# Honig_Sensor_Board_2_01.net
KiCad netlist of a schematic drawn in EAGLE
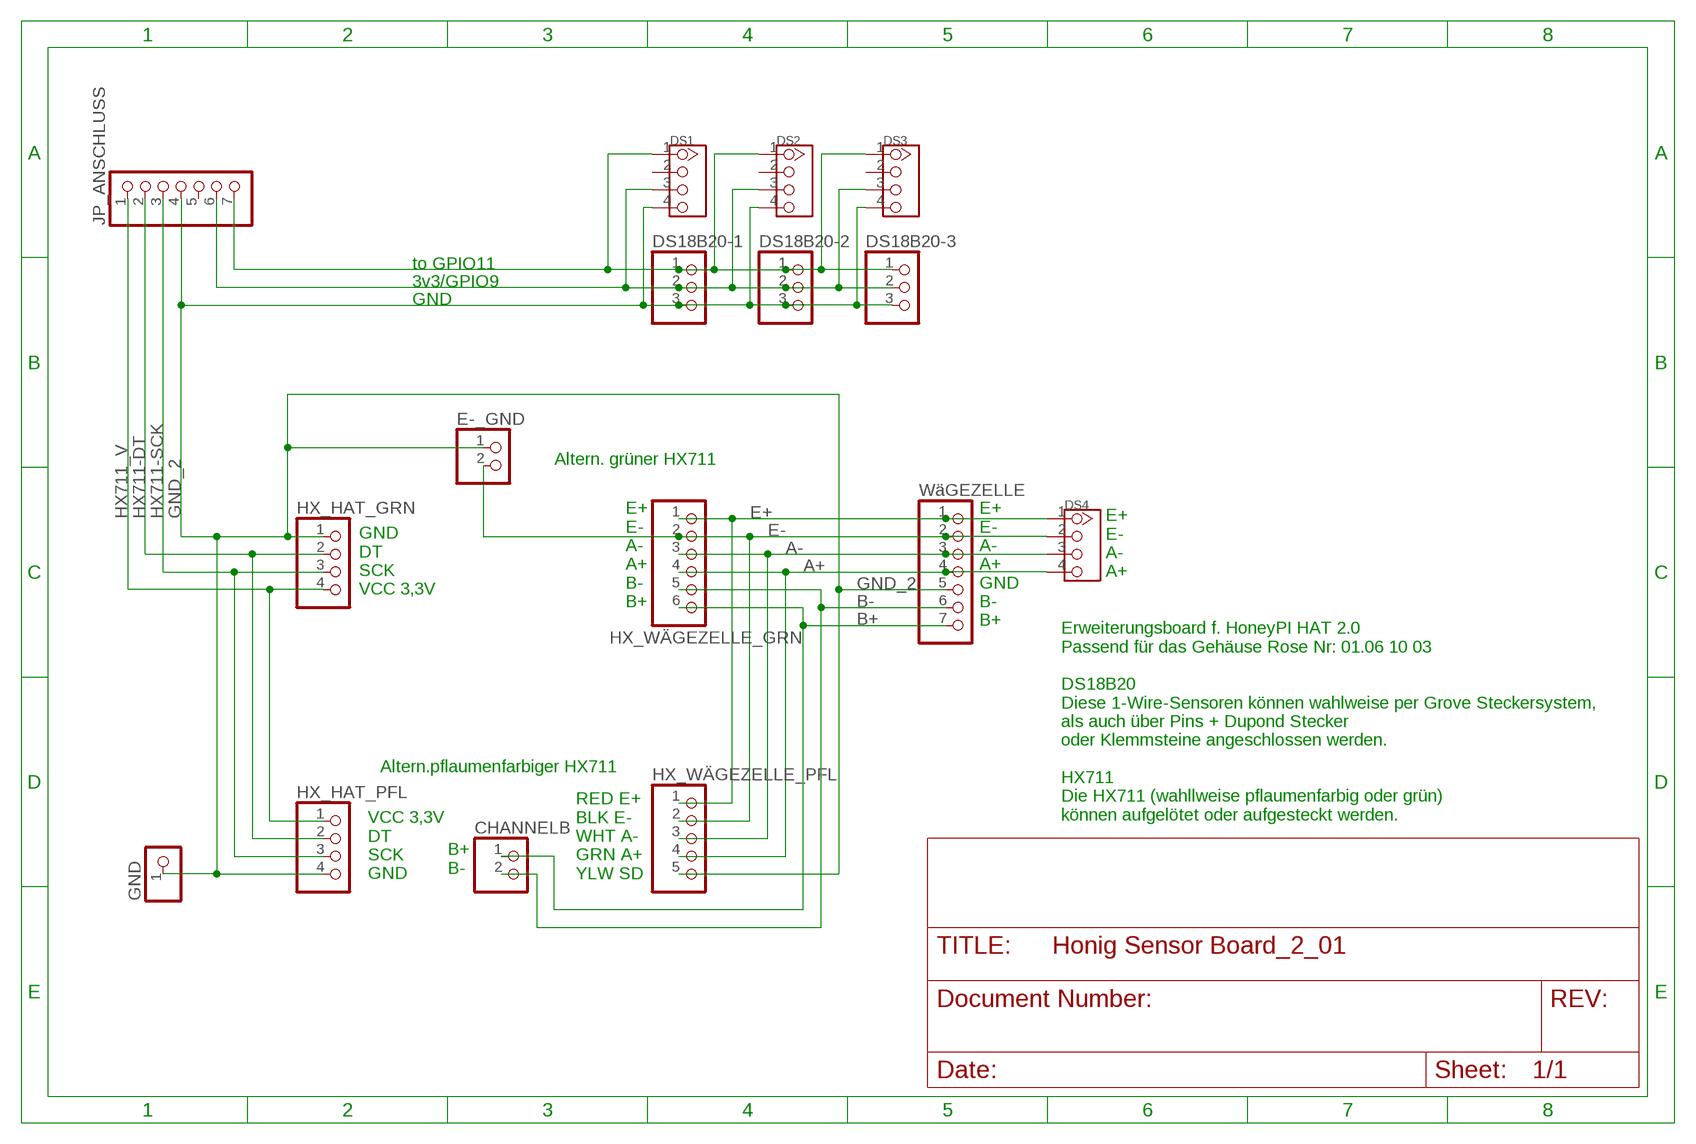
[diagram p0: schematic, sheet 1]

(export (version "E")
  (design (tool "Eeschema 10.0.6"))
  (components
    (comp (ref "CHANNELB")
      (value "PINHD-1X2")
      (footprint "eagle-import:1X02")
      (libsource (lib "eagle-import") (part "PINHD-1X2"))
    )
    (comp (ref "DS1")
      (value "TWIG-4P-2.0-2.0")
      (footprint "eagle-import:4P-2.0")
      (libsource (lib "eagle-import") (part "TWIG-4P-2.0-2.0"))
    )
    (comp (ref "DS2")
      (value "TWIG-4P-2.0-2.0")
      (footprint "eagle-import:4P-2.0")
      (libsource (lib "eagle-import") (part "TWIG-4P-2.0-2.0"))
    )
    (comp (ref "DS3")
      (value "TWIG-4P-2.0-2.0")
      (footprint "eagle-import:4P-2.0")
      (libsource (lib "eagle-import") (part "TWIG-4P-2.0-2.0"))
    )
    (comp (ref "DS4")
      (value "TWIG-4P-2.0-2.0")
      (footprint "eagle-import:4P-2.0")
      (libsource (lib "eagle-import") (part "TWIG-4P-2.0-2.0"))
    )
    (comp (ref "DS18B20-1")
      (value "PINHD-1X3")
      (footprint "eagle-import:1X03")
      (libsource (lib "eagle-import") (part "PINHD-1X3"))
    )
    (comp (ref "DS18B20-2")
      (value "PINHD-1X3")
      (footprint "eagle-import:1X03")
      (libsource (lib "eagle-import") (part "PINHD-1X3"))
    )
    (comp (ref "DS18B20-3")
      (value "PINHD-1X3")
      (footprint "eagle-import:1X03")
      (libsource (lib "eagle-import") (part "PINHD-1X3"))
    )
    (comp (ref "E-_GND")
      (value "PINHD-1X2")
      (footprint "eagle-import:1X02")
      (libsource (lib "eagle-import") (part "PINHD-1X2"))
    )
    (comp (ref "GND")
      (value "PINHD-1X1")
      (footprint "eagle-import:1X01")
      (libsource (lib "eagle-import") (part "PINHD-1X1"))
    )
    (comp (ref "HX_HAT_GRN")
      (value "PINHD-1X4")
      (footprint "eagle-import:1X04")
      (libsource (lib "eagle-import") (part "PINHD-1X4"))
    )
    (comp (ref "HX_HAT_PFL")
      (value "PINHD-1X4")
      (footprint "eagle-import:1X04")
      (libsource (lib "eagle-import") (part "PINHD-1X4"))
    )
    (comp (ref "HX_WÄGEZELLE_GRN")
      (value "PINHD-1X6")
      (footprint "eagle-import:1X06")
      (libsource (lib "eagle-import") (part "PINHD-1X6"))
    )
    (comp (ref "HX_WÄGEZELLE_PFL")
      (value "PINHD-1X5")
      (footprint "eagle-import:1X05")
      (libsource (lib "eagle-import") (part "PINHD-1X5"))
    )
    (comp (ref "JP_ANSCHLUSS")
      (value "PINHD-1X7")
      (footprint "eagle-import:1X07")
      (libsource (lib "eagle-import") (part "PINHD-1X7"))
    )
    (comp (ref "WäGEZELLE")
      (value "PINHD-1X7")
      (footprint "eagle-import:1X07")
      (libsource (lib "eagle-import") (part "PINHD-1X7"))
    )
  )
  (nets
    (net (code "1") (name "/A+") (class "Default")
      (node (ref "DS4") (pin "4") (pinfunction "4_4") (pintype "bidirectional"))
      (node (ref "HX_WÄGEZELLE_GRN") (pin "4") (pinfunction "4_4") (pintype "passive"))
      (node (ref "HX_WÄGEZELLE_PFL") (pin "4") (pinfunction "4_4") (pintype "passive"))
      (node (ref "WäGEZELLE") (pin "4") (pinfunction "4_4") (pintype "passive"))
    )
    (net (code "2") (name "/A-") (class "Default")
      (node (ref "DS4") (pin "3") (pinfunction "3_3") (pintype "bidirectional"))
      (node (ref "HX_WÄGEZELLE_GRN") (pin "3") (pinfunction "3_3") (pintype "passive"))
      (node (ref "HX_WÄGEZELLE_PFL") (pin "3") (pinfunction "3_3") (pintype "passive"))
      (node (ref "WäGEZELLE") (pin "3") (pinfunction "3_3") (pintype "passive"))
    )
    (net (code "3") (name "/B+") (class "Default")
      (node (ref "CHANNELB") (pin "1") (pinfunction "1_1") (pintype "passive"))
      (node (ref "HX_WÄGEZELLE_GRN") (pin "6") (pinfunction "6_6") (pintype "passive"))
      (node (ref "WäGEZELLE") (pin "7") (pinfunction "7_7") (pintype "passive"))
    )
    (net (code "4") (name "/B-") (class "Default")
      (node (ref "CHANNELB") (pin "2") (pinfunction "2_2") (pintype "passive"))
      (node (ref "HX_WÄGEZELLE_GRN") (pin "5") (pinfunction "5_5") (pintype "passive"))
      (node (ref "WäGEZELLE") (pin "6") (pinfunction "6_6") (pintype "passive"))
    )
    (net (code "5") (name "/E+") (class "Default")
      (node (ref "DS4") (pin "1") (pinfunction "1_1") (pintype "bidirectional"))
      (node (ref "HX_WÄGEZELLE_GRN") (pin "1") (pinfunction "1_1") (pintype "passive"))
      (node (ref "HX_WÄGEZELLE_PFL") (pin "1") (pinfunction "1_1") (pintype "passive"))
      (node (ref "WäGEZELLE") (pin "1") (pinfunction "1_1") (pintype "passive"))
    )
    (net (code "6") (name "/E-") (class "Default")
      (node (ref "DS4") (pin "2") (pinfunction "2_2") (pintype "bidirectional"))
      (node (ref "E-_GND") (pin "2") (pinfunction "2_2") (pintype "passive"))
      (node (ref "HX_WÄGEZELLE_GRN") (pin "2") (pinfunction "2_2") (pintype "passive"))
      (node (ref "HX_WÄGEZELLE_PFL") (pin "2") (pinfunction "2_2") (pintype "passive"))
      (node (ref "WäGEZELLE") (pin "2") (pinfunction "2_2") (pintype "passive"))
    )
    (net (code "7") (name "/GND_2") (class "Default")
      (node (ref "DS1") (pin "4") (pinfunction "4_4") (pintype "bidirectional"))
      (node (ref "DS18B20-1") (pin "3") (pinfunction "3_3") (pintype "passive"))
      (node (ref "DS18B20-2") (pin "3") (pinfunction "3_3") (pintype "passive"))
      (node (ref "DS18B20-3") (pin "3") (pinfunction "3_3") (pintype "passive"))
      (node (ref "DS2") (pin "4") (pinfunction "4_4") (pintype "bidirectional"))
      (node (ref "DS3") (pin "4") (pinfunction "4_4") (pintype "bidirectional"))
      (node (ref "E-_GND") (pin "1") (pinfunction "1_1") (pintype "passive"))
      (node (ref "GND") (pin "1") (pinfunction "1_1") (pintype "passive"))
      (node (ref "HX_HAT_GRN") (pin "1") (pinfunction "1_1") (pintype "passive"))
      (node (ref "HX_HAT_PFL") (pin "4") (pinfunction "4_4") (pintype "passive"))
      (node (ref "HX_WÄGEZELLE_PFL") (pin "5") (pinfunction "5_5") (pintype "passive"))
      (node (ref "JP_ANSCHLUSS") (pin "4") (pinfunction "4_4") (pintype "passive"))
      (node (ref "WäGEZELLE") (pin "5") (pinfunction "5_5") (pintype "passive"))
    )
    (net (code "8") (name "/HX711-DT") (class "Default")
      (node (ref "HX_HAT_GRN") (pin "2") (pinfunction "2_2") (pintype "passive"))
      (node (ref "HX_HAT_PFL") (pin "2") (pinfunction "2_2") (pintype "passive"))
      (node (ref "JP_ANSCHLUSS") (pin "2") (pinfunction "2_2") (pintype "passive"))
    )
    (net (code "9") (name "/HX711-SCK") (class "Default")
      (node (ref "HX_HAT_GRN") (pin "3") (pinfunction "3_3") (pintype "passive"))
      (node (ref "HX_HAT_PFL") (pin "3") (pinfunction "3_3") (pintype "passive"))
      (node (ref "JP_ANSCHLUSS") (pin "3") (pinfunction "3_3") (pintype "passive"))
    )
    (net (code "10") (name "/HX711_V") (class "Default")
      (node (ref "HX_HAT_GRN") (pin "4") (pinfunction "4_4") (pintype "passive"))
      (node (ref "HX_HAT_PFL") (pin "1") (pinfunction "1_1") (pintype "passive"))
      (node (ref "JP_ANSCHLUSS") (pin "1") (pinfunction "1_1") (pintype "passive"))
    )
    (net (code "11") (name "Net-(DS1-Pad1)") (class "Default")
      (node (ref "DS1") (pin "1") (pinfunction "1_1") (pintype "bidirectional"))
      (node (ref "DS18B20-1") (pin "1") (pinfunction "1_1") (pintype "passive"))
      (node (ref "DS18B20-2") (pin "1") (pinfunction "1_1") (pintype "passive"))
      (node (ref "DS18B20-3") (pin "1") (pinfunction "1_1") (pintype "passive"))
      (node (ref "DS2") (pin "1") (pinfunction "1_1") (pintype "bidirectional"))
      (node (ref "DS3") (pin "1") (pinfunction "1_1") (pintype "bidirectional"))
      (node (ref "JP_ANSCHLUSS") (pin "7") (pinfunction "7_7") (pintype "passive"))
    )
    (net (code "12") (name "Net-(DS1-Pad3)") (class "Default")
      (node (ref "DS1") (pin "3") (pinfunction "3_3") (pintype "bidirectional"))
      (node (ref "DS18B20-1") (pin "2") (pinfunction "2_2") (pintype "passive"))
      (node (ref "DS18B20-2") (pin "2") (pinfunction "2_2") (pintype "passive"))
      (node (ref "DS18B20-3") (pin "2") (pinfunction "2_2") (pintype "passive"))
      (node (ref "DS2") (pin "3") (pinfunction "3_3") (pintype "bidirectional"))
      (node (ref "DS3") (pin "3") (pinfunction "3_3") (pintype "bidirectional"))
      (node (ref "JP_ANSCHLUSS") (pin "6") (pinfunction "6_6") (pintype "passive"))
    )
    (net (code "13") (name "unconnected-(DS1-Pad2)") (class "Default")
      (node (ref "DS1") (pin "2") (pinfunction "2_2") (pintype "bidirectional"))
    )
    (net (code "14") (name "unconnected-(DS2-Pad2)") (class "Default")
      (node (ref "DS2") (pin "2") (pinfunction "2_2") (pintype "bidirectional"))
    )
    (net (code "15") (name "unconnected-(DS3-Pad2)") (class "Default")
      (node (ref "DS3") (pin "2") (pinfunction "2_2") (pintype "bidirectional"))
    )
    (net (code "16") (name "unconnected-(JP_ANSCHLUSS-Pad5)") (class "Default")
      (node (ref "JP_ANSCHLUSS") (pin "5") (pinfunction "5_5") (pintype "passive"))
    )
  )
)
